# ProtoShieldBasic.net
KiCad netlist of a schematic drawn in EAGLE
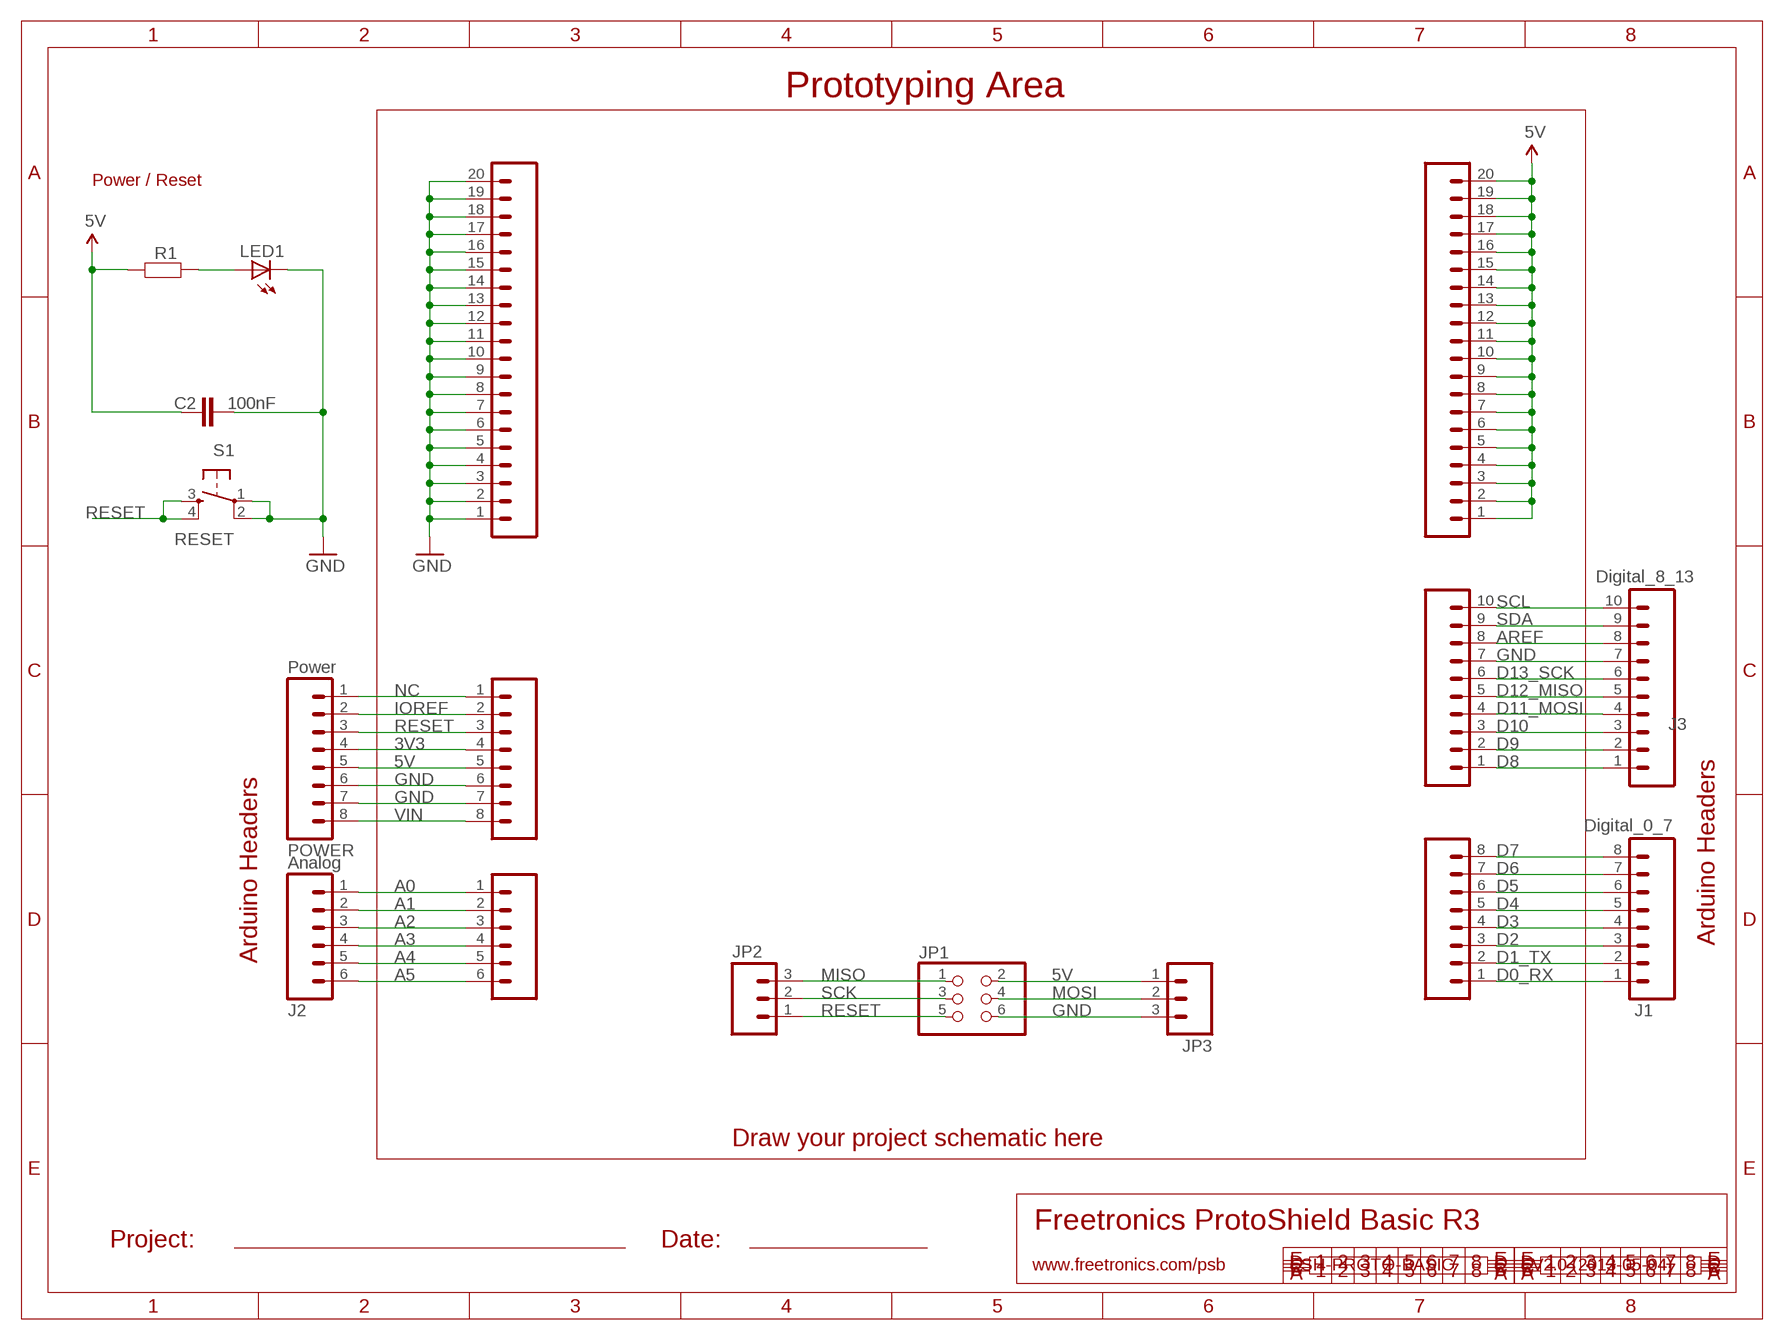
[diagram p0: schematic, sheet 1]

(export (version "E")
  (design (tool "Eeschema 10.0.6"))
  (components
    (comp (ref "C2")
      (value "100nF")
      (footprint "eagle-import:CAP-PTH-SMALL")
      (libsource (lib "eagle-import") (part "CAPPTH"))
    )
    (comp (ref "J1")
      (value "Digital_0_7")
      (footprint "eagle-import:1X08")
      (libsource (lib "eagle-import") (part "M08"))
    )
    (comp (ref "J2")
      (value "Analog")
      (footprint "eagle-import:1X06")
      (libsource (lib "eagle-import") (part "M06SIP"))
    )
    (comp (ref "J3")
      (value "Digital_8_13")
      (footprint "eagle-import:1X10")
      (libsource (lib "eagle-import") (part "M100.1"))
    )
    (comp (ref "JP1")
      (value "PINHD-2X3")
      (footprint "eagle-import:2X03")
      (libsource (lib "eagle-import") (part "PINHD-2X3"))
    )
    (comp (ref "JP2")
      (value "M03PTH")
      (footprint "eagle-import:1X03")
      (libsource (lib "eagle-import") (part "M03PTH"))
    )
    (comp (ref "JP3")
      (value "M03PTH")
      (footprint "eagle-import:1X03")
      (libsource (lib "eagle-import") (part "M03PTH"))
    )
    (comp (ref "LED1")
      (value "LED3MM")
      (footprint "eagle-import:LED3MM")
      (libsource (lib "eagle-import") (part "LED3MM"))
    )
    (comp (ref "PADS_5V")
      (value "M20")
      (footprint "eagle-import:1X20")
      (libsource (lib "eagle-import") (part "M20"))
    )
    (comp (ref "PADS_GND")
      (value "M20")
      (footprint "eagle-import:1X20")
      (libsource (lib "eagle-import") (part "M20"))
    )
    (comp (ref "POWER")
      (value "Power")
      (footprint "eagle-import:1X08")
      (libsource (lib "eagle-import") (part "freetronics-original_M08"))
    )
    (comp (ref "R1")
      (value "RESISTORPTH1")
      (footprint "eagle-import:AXIAL-0.3")
      (libsource (lib "eagle-import") (part "RESISTORPTH1"))
    )
    (comp (ref "S1")
      (value "RESET")
      (footprint "eagle-import:TACTILE-PTH")
      (libsource (lib "eagle-import") (part "TAC_SWITCHPTH"))
    )
    (comp (ref "SL1")
      (value "Digital_0_7")
      (footprint "eagle-import:1X08")
      (libsource (lib "eagle-import") (part "M08"))
    )
    (comp (ref "SL2")
      (value "Analog")
      (footprint "eagle-import:1X06")
      (libsource (lib "eagle-import") (part "M06SIP"))
    )
    (comp (ref "SL3")
      (value "Digital_8_13")
      (footprint "eagle-import:1X10")
      (libsource (lib "eagle-import") (part "M100.1"))
    )
    (comp (ref "SLP")
      (value "Power")
      (footprint "eagle-import:1X08")
      (libsource (lib "eagle-import") (part "freetronics-original_M08"))
    )
  )
  (nets
    (net (code "1") (name "/3V3") (class "Default")
      (node (ref "POWER") (pin "4") (pinfunction "4_4") (pintype "passive"))
      (node (ref "SLP") (pin "4") (pinfunction "4_4") (pintype "passive"))
    )
    (net (code "2") (name "/A0") (class "Default")
      (node (ref "J2") (pin "1") (pinfunction "1_1") (pintype "passive"))
      (node (ref "SL2") (pin "1") (pinfunction "1_1") (pintype "passive"))
    )
    (net (code "3") (name "/A1") (class "Default")
      (node (ref "J2") (pin "2") (pinfunction "2_2") (pintype "passive"))
      (node (ref "SL2") (pin "2") (pinfunction "2_2") (pintype "passive"))
    )
    (net (code "4") (name "/A2") (class "Default")
      (node (ref "J2") (pin "3") (pinfunction "3_3") (pintype "passive"))
      (node (ref "SL2") (pin "3") (pinfunction "3_3") (pintype "passive"))
    )
    (net (code "5") (name "/A3") (class "Default")
      (node (ref "J2") (pin "4") (pinfunction "4_4") (pintype "passive"))
      (node (ref "SL2") (pin "4") (pinfunction "4_4") (pintype "passive"))
    )
    (net (code "6") (name "/A4") (class "Default")
      (node (ref "J2") (pin "5") (pinfunction "5_5") (pintype "passive"))
      (node (ref "SL2") (pin "5") (pinfunction "5_5") (pintype "passive"))
    )
    (net (code "7") (name "/A5") (class "Default")
      (node (ref "J2") (pin "6") (pinfunction "6_6") (pintype "passive"))
      (node (ref "SL2") (pin "6") (pinfunction "6_6") (pintype "passive"))
    )
    (net (code "8") (name "/AREF") (class "Default")
      (node (ref "J3") (pin "8") (pinfunction "8_8") (pintype "passive"))
      (node (ref "SL3") (pin "8") (pinfunction "8_8") (pintype "passive"))
    )
    (net (code "9") (name "/D0_RX") (class "Default")
      (node (ref "J1") (pin "1") (pinfunction "1_1") (pintype "passive"))
      (node (ref "SL1") (pin "1") (pinfunction "1_1") (pintype "passive"))
    )
    (net (code "10") (name "/D1_TX") (class "Default")
      (node (ref "J1") (pin "2") (pinfunction "2_2") (pintype "passive"))
      (node (ref "SL1") (pin "2") (pinfunction "2_2") (pintype "passive"))
    )
    (net (code "11") (name "/D2") (class "Default")
      (node (ref "J1") (pin "3") (pinfunction "3_3") (pintype "passive"))
      (node (ref "SL1") (pin "3") (pinfunction "3_3") (pintype "passive"))
    )
    (net (code "12") (name "/D3") (class "Default")
      (node (ref "J1") (pin "4") (pinfunction "4_4") (pintype "passive"))
      (node (ref "SL1") (pin "4") (pinfunction "4_4") (pintype "passive"))
    )
    (net (code "13") (name "/D4") (class "Default")
      (node (ref "J1") (pin "5") (pinfunction "5_5") (pintype "passive"))
      (node (ref "SL1") (pin "5") (pinfunction "5_5") (pintype "passive"))
    )
    (net (code "14") (name "/D5") (class "Default")
      (node (ref "J1") (pin "6") (pinfunction "6_6") (pintype "passive"))
      (node (ref "SL1") (pin "6") (pinfunction "6_6") (pintype "passive"))
    )
    (net (code "15") (name "/D6") (class "Default")
      (node (ref "J1") (pin "7") (pinfunction "7_7") (pintype "passive"))
      (node (ref "SL1") (pin "7") (pinfunction "7_7") (pintype "passive"))
    )
    (net (code "16") (name "/D7") (class "Default")
      (node (ref "J1") (pin "8") (pinfunction "8_8") (pintype "passive"))
      (node (ref "SL1") (pin "8") (pinfunction "8_8") (pintype "passive"))
    )
    (net (code "17") (name "/D8") (class "Default")
      (node (ref "J3") (pin "1") (pinfunction "1_1") (pintype "passive"))
      (node (ref "SL3") (pin "1") (pinfunction "1_1") (pintype "passive"))
    )
    (net (code "18") (name "/D9") (class "Default")
      (node (ref "J3") (pin "2") (pinfunction "2_2") (pintype "passive"))
      (node (ref "SL3") (pin "2") (pinfunction "2_2") (pintype "passive"))
    )
    (net (code "19") (name "/D10") (class "Default")
      (node (ref "J3") (pin "3") (pinfunction "3_3") (pintype "passive"))
      (node (ref "SL3") (pin "3") (pinfunction "3_3") (pintype "passive"))
    )
    (net (code "20") (name "/D11_MOSI") (class "Default")
      (node (ref "J3") (pin "4") (pinfunction "4_4") (pintype "passive"))
      (node (ref "SL3") (pin "4") (pinfunction "4_4") (pintype "passive"))
    )
    (net (code "21") (name "/D12_MISO") (class "Default")
      (node (ref "J3") (pin "5") (pinfunction "5_5") (pintype "passive"))
      (node (ref "SL3") (pin "5") (pinfunction "5_5") (pintype "passive"))
    )
    (net (code "22") (name "/D13_SCK") (class "Default")
      (node (ref "J3") (pin "6") (pinfunction "6_6") (pintype "passive"))
      (node (ref "SL3") (pin "6") (pinfunction "6_6") (pintype "passive"))
    )
    (net (code "23") (name "/IOREF") (class "Default")
      (node (ref "POWER") (pin "2") (pinfunction "2_2") (pintype "passive"))
      (node (ref "SLP") (pin "2") (pinfunction "2_2") (pintype "passive"))
    )
    (net (code "24") (name "/MISO") (class "Default")
      (node (ref "JP1") (pin "1") (pinfunction "1_1") (pintype "passive"))
      (node (ref "JP2") (pin "3") (pinfunction "3_3") (pintype "passive"))
    )
    (net (code "25") (name "/MOSI") (class "Default")
      (node (ref "JP1") (pin "4") (pinfunction "4_4") (pintype "passive"))
      (node (ref "JP3") (pin "2") (pinfunction "2_2") (pintype "passive"))
    )
    (net (code "26") (name "/NC") (class "Default")
      (node (ref "POWER") (pin "1") (pinfunction "1_1") (pintype "passive"))
      (node (ref "SLP") (pin "1") (pinfunction "1_1") (pintype "passive"))
    )
    (net (code "27") (name "/RESET") (class "Default")
      (node (ref "JP1") (pin "5") (pinfunction "5_5") (pintype "passive"))
      (node (ref "JP2") (pin "1") (pinfunction "1_1") (pintype "passive"))
      (node (ref "POWER") (pin "3") (pinfunction "3_3") (pintype "passive"))
      (node (ref "S1") (pin "3") (pinfunction "3_3") (pintype "passive"))
      (node (ref "S1") (pin "4") (pinfunction "4_4") (pintype "passive"))
      (node (ref "SLP") (pin "3") (pinfunction "3_3") (pintype "passive"))
    )
    (net (code "28") (name "/SCK") (class "Default")
      (node (ref "JP1") (pin "3") (pinfunction "3_3") (pintype "passive"))
      (node (ref "JP2") (pin "2") (pinfunction "2_2") (pintype "passive"))
    )
    (net (code "29") (name "/SCL") (class "Default")
      (node (ref "J3") (pin "10") (pinfunction "10_10") (pintype "passive"))
      (node (ref "SL3") (pin "10") (pinfunction "10_10") (pintype "passive"))
    )
    (net (code "30") (name "/SDA") (class "Default")
      (node (ref "J3") (pin "9") (pinfunction "9_9") (pintype "passive"))
      (node (ref "SL3") (pin "9") (pinfunction "9_9") (pintype "passive"))
    )
    (net (code "31") (name "/VIN") (class "Default")
      (node (ref "POWER") (pin "8") (pinfunction "8_8") (pintype "passive"))
      (node (ref "SLP") (pin "8") (pinfunction "8_8") (pintype "passive"))
    )
    (net (code "32") (name "5V") (class "Default")
      (node (ref "C2") (pin "1") (pinfunction "1_1") (pintype "passive"))
      (node (ref "JP1") (pin "2") (pinfunction "2_2") (pintype "passive"))
      (node (ref "JP3") (pin "1") (pinfunction "1_1") (pintype "passive"))
      (node (ref "PADS_5V") (pin "1") (pinfunction "1_1") (pintype "passive"))
      (node (ref "PADS_5V") (pin "10") (pinfunction "10_10") (pintype "passive"))
      (node (ref "PADS_5V") (pin "11") (pinfunction "11_11") (pintype "passive"))
      (node (ref "PADS_5V") (pin "12") (pinfunction "12_12") (pintype "passive"))
      (node (ref "PADS_5V") (pin "13") (pinfunction "13_13") (pintype "passive"))
      (node (ref "PADS_5V") (pin "14") (pinfunction "14_14") (pintype "passive"))
      (node (ref "PADS_5V") (pin "15") (pinfunction "15_15") (pintype "passive"))
      (node (ref "PADS_5V") (pin "16") (pinfunction "16_16") (pintype "passive"))
      (node (ref "PADS_5V") (pin "17") (pinfunction "17_17") (pintype "passive"))
      (node (ref "PADS_5V") (pin "18") (pinfunction "18_18") (pintype "passive"))
      (node (ref "PADS_5V") (pin "19") (pinfunction "19_19") (pintype "passive"))
      (node (ref "PADS_5V") (pin "2") (pinfunction "2_2") (pintype "passive"))
      (node (ref "PADS_5V") (pin "20") (pinfunction "20_20") (pintype "passive"))
      (node (ref "PADS_5V") (pin "3") (pinfunction "3_3") (pintype "passive"))
      (node (ref "PADS_5V") (pin "4") (pinfunction "4_4") (pintype "passive"))
      (node (ref "PADS_5V") (pin "5") (pinfunction "5_5") (pintype "passive"))
      (node (ref "PADS_5V") (pin "6") (pinfunction "6_6") (pintype "passive"))
      (node (ref "PADS_5V") (pin "7") (pinfunction "7_7") (pintype "passive"))
      (node (ref "PADS_5V") (pin "8") (pinfunction "8_8") (pintype "passive"))
      (node (ref "PADS_5V") (pin "9") (pinfunction "9_9") (pintype "passive"))
      (node (ref "POWER") (pin "5") (pinfunction "5_5") (pintype "passive"))
      (node (ref "R1") (pin "P$1") (pinfunction "1_P$1") (pintype "passive"))
      (node (ref "SLP") (pin "5") (pinfunction "5_5") (pintype "passive"))
    )
    (net (code "33") (name "GND") (class "Default")
      (node (ref "C2") (pin "2") (pinfunction "2_2") (pintype "passive"))
      (node (ref "J3") (pin "7") (pinfunction "7_7") (pintype "passive"))
      (node (ref "JP1") (pin "6") (pinfunction "6_6") (pintype "passive"))
      (node (ref "JP3") (pin "3") (pinfunction "3_3") (pintype "passive"))
      (node (ref "LED1") (pin "K") (pinfunction "C_K") (pintype "passive"))
      (node (ref "PADS_GND") (pin "1") (pinfunction "1_1") (pintype "passive"))
      (node (ref "PADS_GND") (pin "10") (pinfunction "10_10") (pintype "passive"))
      (node (ref "PADS_GND") (pin "11") (pinfunction "11_11") (pintype "passive"))
      (node (ref "PADS_GND") (pin "12") (pinfunction "12_12") (pintype "passive"))
      (node (ref "PADS_GND") (pin "13") (pinfunction "13_13") (pintype "passive"))
      (node (ref "PADS_GND") (pin "14") (pinfunction "14_14") (pintype "passive"))
      (node (ref "PADS_GND") (pin "15") (pinfunction "15_15") (pintype "passive"))
      (node (ref "PADS_GND") (pin "16") (pinfunction "16_16") (pintype "passive"))
      (node (ref "PADS_GND") (pin "17") (pinfunction "17_17") (pintype "passive"))
      (node (ref "PADS_GND") (pin "18") (pinfunction "18_18") (pintype "passive"))
      (node (ref "PADS_GND") (pin "19") (pinfunction "19_19") (pintype "passive"))
      (node (ref "PADS_GND") (pin "2") (pinfunction "2_2") (pintype "passive"))
      (node (ref "PADS_GND") (pin "20") (pinfunction "20_20") (pintype "passive"))
      (node (ref "PADS_GND") (pin "3") (pinfunction "3_3") (pintype "passive"))
      (node (ref "PADS_GND") (pin "4") (pinfunction "4_4") (pintype "passive"))
      (node (ref "PADS_GND") (pin "5") (pinfunction "5_5") (pintype "passive"))
      (node (ref "PADS_GND") (pin "6") (pinfunction "6_6") (pintype "passive"))
      (node (ref "PADS_GND") (pin "7") (pinfunction "7_7") (pintype "passive"))
      (node (ref "PADS_GND") (pin "8") (pinfunction "8_8") (pintype "passive"))
      (node (ref "PADS_GND") (pin "9") (pinfunction "9_9") (pintype "passive"))
      (node (ref "POWER") (pin "6") (pinfunction "6_6") (pintype "passive"))
      (node (ref "POWER") (pin "7") (pinfunction "7_7") (pintype "passive"))
      (node (ref "S1") (pin "1") (pinfunction "1_1") (pintype "passive"))
      (node (ref "S1") (pin "2") (pinfunction "2_2") (pintype "passive"))
      (node (ref "SL3") (pin "7") (pinfunction "7_7") (pintype "passive"))
      (node (ref "SLP") (pin "6") (pinfunction "6_6") (pintype "passive"))
      (node (ref "SLP") (pin "7") (pinfunction "7_7") (pintype "passive"))
    )
    (net (code "34") (name "Net-(R1-2)") (class "Default")
      (node (ref "LED1") (pin "A") (pinfunction "A_A") (pintype "passive"))
      (node (ref "R1") (pin "P$2") (pinfunction "2_P$2") (pintype "passive"))
    )
  )
)
